# capacitance_touch_project.net
KiCad netlist of a schematic drawn in EAGLE
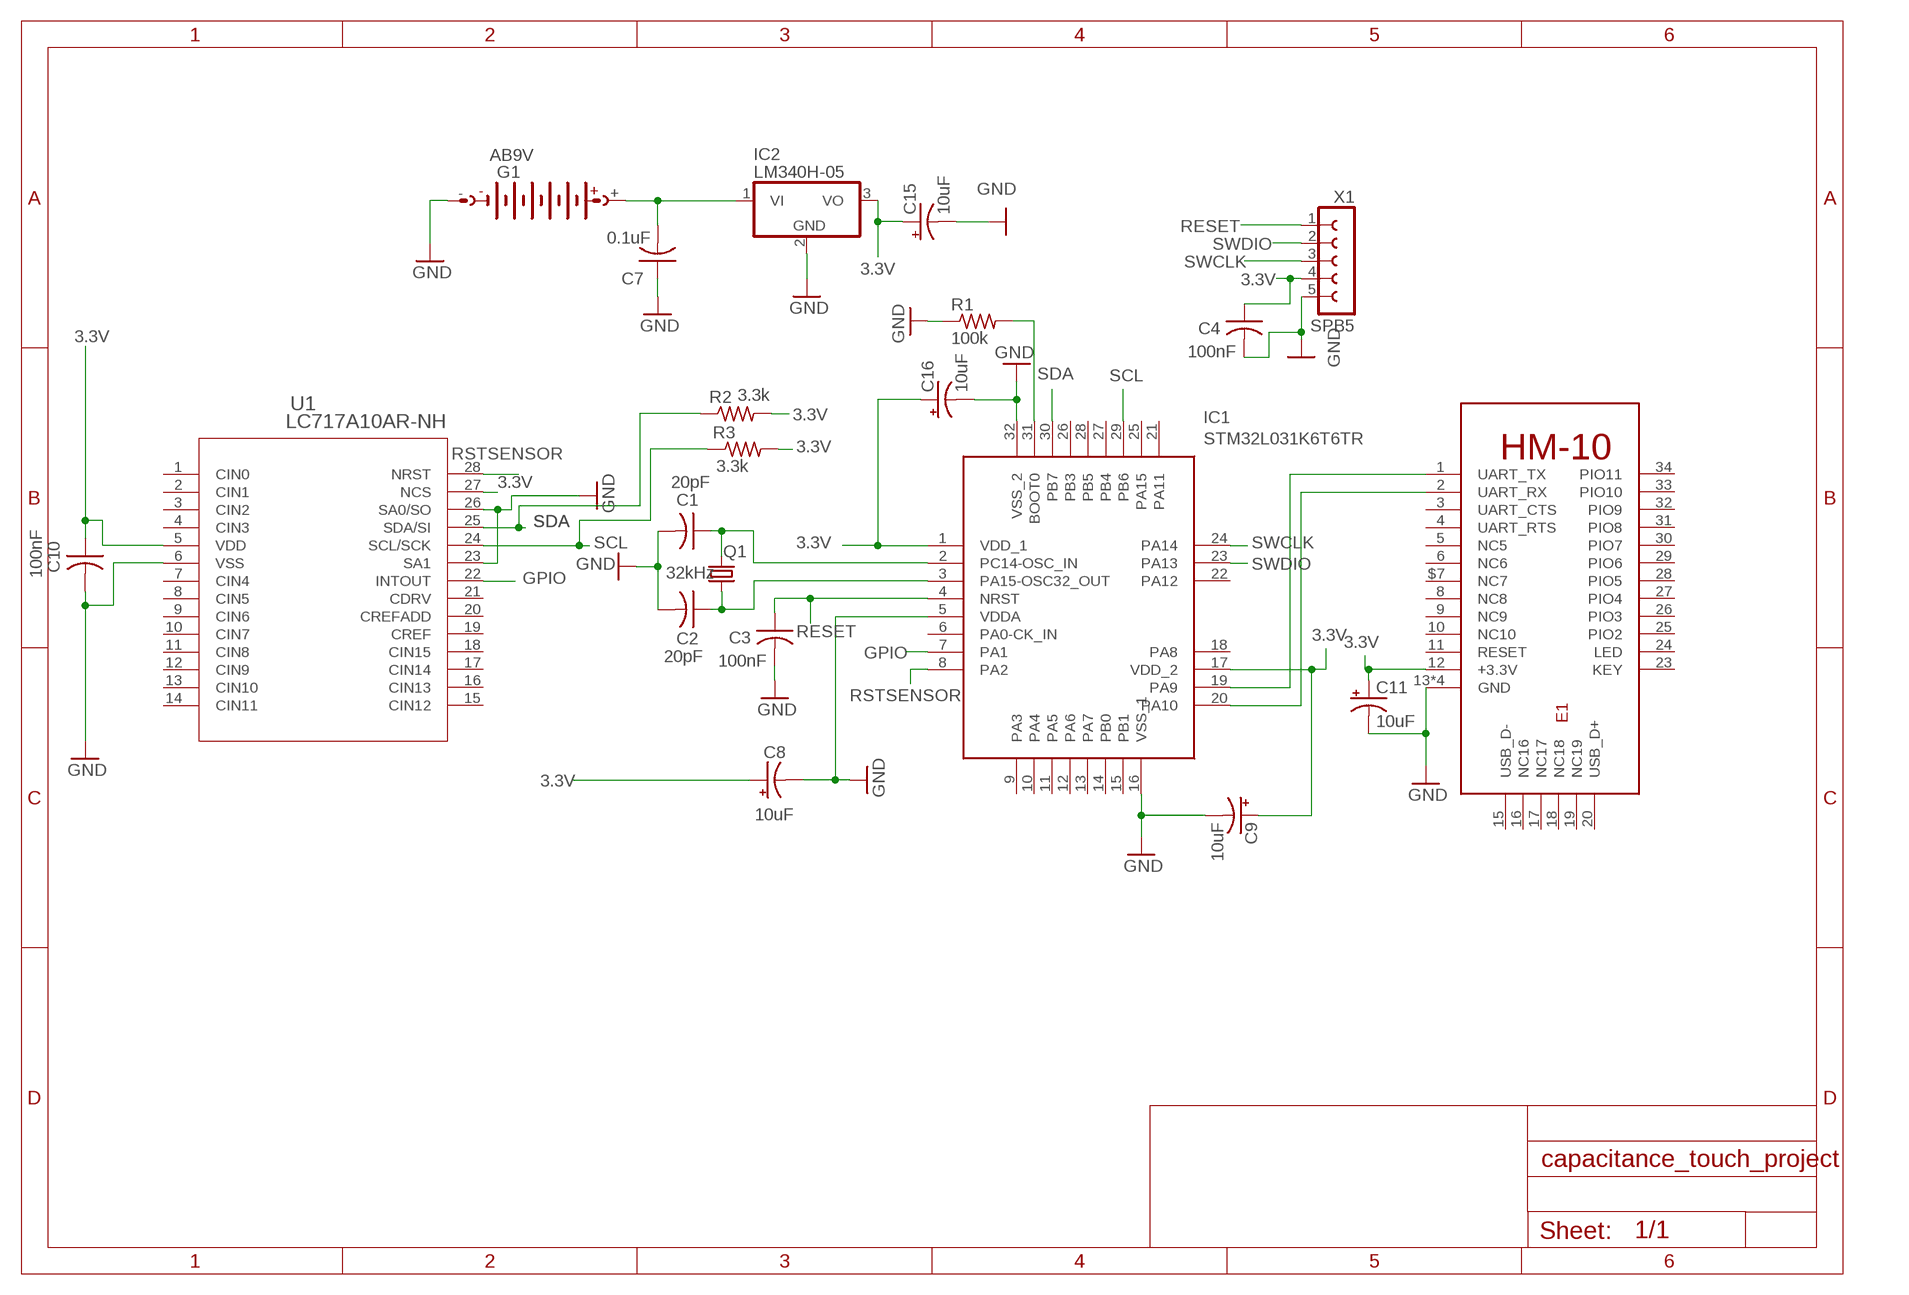
[diagram p0: schematic, sheet 1]

(export (version "E")
  (design (tool "Eeschema 10.0.6"))
  (components
    (comp (ref "C1")
      (value "20pF")
      (footprint "eagle-import:C0805")
      (libsource (lib "eagle-import") (part "C-USC0805"))
    )
    (comp (ref "C2")
      (value "20pF")
      (footprint "eagle-import:C0805")
      (libsource (lib "eagle-import") (part "C-USC0805"))
    )
    (comp (ref "C3")
      (value "100nF")
      (footprint "eagle-import:C0805")
      (libsource (lib "eagle-import") (part "C-USC0805"))
    )
    (comp (ref "C4")
      (value "100nF")
      (footprint "eagle-import:C0805")
      (libsource (lib "eagle-import") (part "C-USC0805"))
    )
    (comp (ref "C7")
      (value "0.1uF")
      (footprint "eagle-import:C0805")
      (libsource (lib "eagle-import") (part "C-USC0805"))
    )
    (comp (ref "C8")
      (value "10uF")
      (footprint "eagle-import:E2-5")
      (libsource (lib "eagle-import") (part "CPOL-USE2-5"))
    )
    (comp (ref "C9")
      (value "10uF")
      (footprint "eagle-import:E2-5")
      (libsource (lib "eagle-import") (part "CPOL-USE2-5"))
    )
    (comp (ref "C10")
      (value "100nF")
      (footprint "eagle-import:C0805")
      (libsource (lib "eagle-import") (part "C-USC0805"))
    )
    (comp (ref "C11")
      (value "10uF")
      (footprint "eagle-import:E2-5")
      (libsource (lib "eagle-import") (part "CPOL-USE2-5"))
    )
    (comp (ref "C15")
      (value "10uF")
      (footprint "eagle-import:E2-5")
      (libsource (lib "eagle-import") (part "CPOL-USE2-5"))
    )
    (comp (ref "C16")
      (value "10uF")
      (footprint "eagle-import:E2-5")
      (libsource (lib "eagle-import") (part "CPOL-USE2-5"))
    )
    (comp (ref "E1")
      (value "HM-10-BOARD")
      (footprint "eagle-import:26.9X13X2.2_BOARD")
      (libsource (lib "eagle-import") (part "HM-10-BOARD"))
    )
    (comp (ref "G1")
      (value "AB9V")
      (footprint "eagle-import:AB9V")
      (libsource (lib "eagle-import") (part "AB9V"))
    )
    (comp (ref "IC1")
      (value "STM32L031K6T6TR")
      (footprint "eagle-import:QFP80P900X900X160-32N")
      (fields (field (name "MOUSER_PART_NUMBER") "511-STM32L031K6T6TR"))
      (libsource (lib "eagle-import") (part "STM32L031K6T6TR"))
    )
    (comp (ref "IC2")
      (value "LM340H-05")
      (footprint "eagle-import:TO220H")
      (libsource (lib "eagle-import") (part "LM340?-H05"))
    )
    (comp (ref "Q1")
      (value "32kHz")
      (footprint "eagle-import:HC49_S")
      (libsource (lib "eagle-import") (part "CRYSTALHC49S"))
    )
    (comp (ref "R1")
      (value "100k")
      (footprint "eagle-import:0204_7")
      (libsource (lib "eagle-import") (part "R-US_0204/7"))
    )
    (comp (ref "R2")
      (value "3.3k")
      (footprint "eagle-import:0204_7")
      (libsource (lib "eagle-import") (part "R-US_0204/7"))
    )
    (comp (ref "R3")
      (value "3.3k")
      (footprint "eagle-import:0204_7")
      (libsource (lib "eagle-import") (part "R-US_0204/7"))
    )
    (comp (ref "U1")
      (value "LC717A10AR-NH")
      (footprint "eagle-import:VCT28_3P5X3P5_ONS")
      (fields (field (name "COPYRIGHT") "Copyright (C) 2018 Accelerated Designs. All rights reserved"))
      (libsource (lib "eagle-import") (part "LC717A10AR-NH"))
    )
    (comp (ref "X1")
      (value "SPB5")
      (footprint "eagle-import:SPB5")
      (libsource (lib "eagle-import") (part "SPB5"))
    )
  )
  (nets
    (net (code "1") (name "/3.3V") (class "Default")
      (node (ref "C10") (pin "1") (pinfunction "1_1") (pintype "passive"))
      (node (ref "C11") (pin "+") (pinfunction "+_+") (pintype "passive"))
      (node (ref "C15") (pin "+") (pinfunction "+_+") (pintype "passive"))
      (node (ref "C16") (pin "+") (pinfunction "+_+") (pintype "passive"))
      (node (ref "C4") (pin "1") (pinfunction "1_1") (pintype "passive"))
      (node (ref "C8") (pin "+") (pinfunction "+_+") (pintype "passive"))
      (node (ref "C9") (pin "+") (pinfunction "+_+") (pintype "passive"))
      (node (ref "E1") (pin "12") (pinfunction "+3.3V_12") (pintype "bidirectional"))
      (node (ref "IC1") (pin "1") (pinfunction "VDD_1_1") (pintype "bidirectional"))
      (node (ref "IC1") (pin "17") (pinfunction "VDD_2_17") (pintype "bidirectional"))
      (node (ref "IC2") (pin "3") (pinfunction "VO_3") (pintype "passive"))
      (node (ref "R2") (pin "2") (pinfunction "2_2") (pintype "passive"))
      (node (ref "R3") (pin "2") (pinfunction "2_2") (pintype "passive"))
      (node (ref "U1") (pin "27") (pinfunction "NCS_27") (pintype "input"))
      (node (ref "U1") (pin "5") (pinfunction "VDD_5") (pintype "power_in"))
      (node (ref "X1") (pin "4") (pinfunction "4_4") (pintype "passive"))
    )
    (net (code "2") (name "/GPIO") (class "Default")
      (node (ref "IC1") (pin "7") (pinfunction "PA1_7") (pintype "bidirectional"))
      (node (ref "U1") (pin "22") (pinfunction "INTOUT_22") (pintype "output"))
    )
    (net (code "3") (name "/RESET") (class "Default")
      (node (ref "C3") (pin "1") (pinfunction "1_1") (pintype "passive"))
      (node (ref "IC1") (pin "4") (pinfunction "NRST_4") (pintype "bidirectional"))
      (node (ref "X1") (pin "1") (pinfunction "1_1") (pintype "passive"))
    )
    (net (code "4") (name "/RSTSENSOR") (class "Default")
      (node (ref "IC1") (pin "8") (pinfunction "PA2_8") (pintype "bidirectional"))
      (node (ref "U1") (pin "28") (pinfunction "NRST_28") (pintype "input"))
    )
    (net (code "5") (name "/SCL") (class "Default")
      (node (ref "IC1") (pin "29") (pinfunction "PB6_29") (pintype "bidirectional"))
      (node (ref "R3") (pin "1") (pinfunction "1_1") (pintype "passive"))
      (node (ref "U1") (pin "24") (pinfunction "SCL/SCK_24") (pintype "input"))
    )
    (net (code "6") (name "/SDA") (class "Default")
      (node (ref "IC1") (pin "30") (pinfunction "PB7_30") (pintype "bidirectional"))
      (node (ref "R2") (pin "1") (pinfunction "1_1") (pintype "passive"))
      (node (ref "U1") (pin "25") (pinfunction "SDA/SI_25") (pintype "bidirectional"))
    )
    (net (code "7") (name "/SWCLK") (class "Default")
      (node (ref "IC1") (pin "24") (pinfunction "PA14_24") (pintype "bidirectional"))
      (node (ref "X1") (pin "3") (pinfunction "3_3") (pintype "passive"))
    )
    (net (code "8") (name "/SWDIO") (class "Default")
      (node (ref "IC1") (pin "23") (pinfunction "PA13_23") (pintype "bidirectional"))
      (node (ref "X1") (pin "2") (pinfunction "2_2") (pintype "passive"))
    )
    (net (code "9") (name "GND") (class "Default")
      (node (ref "C1") (pin "2") (pinfunction "2_2") (pintype "passive"))
      (node (ref "C10") (pin "2") (pinfunction "2_2") (pintype "passive"))
      (node (ref "C11") (pin "-") (pinfunction "-_-") (pintype "passive"))
      (node (ref "C15") (pin "-") (pinfunction "-_-") (pintype "passive"))
      (node (ref "C16") (pin "-") (pinfunction "-_-") (pintype "passive"))
      (node (ref "C2") (pin "2") (pinfunction "2_2") (pintype "passive"))
      (node (ref "C3") (pin "2") (pinfunction "2_2") (pintype "passive"))
      (node (ref "C4") (pin "2") (pinfunction "2_2") (pintype "passive"))
      (node (ref "C7") (pin "1") (pinfunction "1_1") (pintype "passive"))
      (node (ref "C8") (pin "-") (pinfunction "-_-") (pintype "passive"))
      (node (ref "C9") (pin "-") (pinfunction "-_-") (pintype "passive"))
      (node (ref "E1") (pin "13") (pinfunction "GND_13") (pintype "bidirectional"))
      (node (ref "E1") (pin "14") (pinfunction "GND_14") (pintype "bidirectional"))
      (node (ref "E1") (pin "21") (pinfunction "GND_21") (pintype "bidirectional"))
      (node (ref "E1") (pin "22") (pinfunction "GND_22") (pintype "bidirectional"))
      (node (ref "G1") (pin "-") (pinfunction "-_-") (pintype "passive"))
      (node (ref "IC1") (pin "16") (pinfunction "VSS_1_16") (pintype "bidirectional"))
      (node (ref "IC1") (pin "32") (pinfunction "VSS_2_32") (pintype "bidirectional"))
      (node (ref "IC1") (pin "5") (pinfunction "VDDA_5") (pintype "bidirectional"))
      (node (ref "IC2") (pin "2") (pinfunction "GND_2") (pintype "passive"))
      (node (ref "R1") (pin "1") (pinfunction "1_1") (pintype "passive"))
      (node (ref "U1") (pin "23") (pinfunction "SA1_23") (pintype "input"))
      (node (ref "U1") (pin "26") (pinfunction "SA0/SO_26") (pintype "bidirectional"))
      (node (ref "U1") (pin "6") (pinfunction "VSS_6") (pintype "passive"))
      (node (ref "X1") (pin "5") (pinfunction "5_5") (pintype "passive"))
    )
    (net (code "10") (name "Net-(E1-UART_RX)") (class "Default")
      (node (ref "E1") (pin "2") (pinfunction "UART_RX_2") (pintype "bidirectional"))
      (node (ref "IC1") (pin "20") (pinfunction "PA10_20") (pintype "bidirectional"))
    )
    (net (code "11") (name "Net-(E1-UART_TX)") (class "Default")
      (node (ref "E1") (pin "1") (pinfunction "UART_TX_1") (pintype "bidirectional"))
      (node (ref "IC1") (pin "19") (pinfunction "PA9_19") (pintype "bidirectional"))
    )
    (net (code "12") (name "Net-(IC1-BOOT0)") (class "Default")
      (node (ref "IC1") (pin "31") (pinfunction "BOOT0_31") (pintype "bidirectional"))
      (node (ref "R1") (pin "2") (pinfunction "2_2") (pintype "passive"))
    )
    (net (code "13") (name "Net-(IC1-PA15-OSC32_OUT)") (class "Default")
      (node (ref "C2") (pin "1") (pinfunction "1_1") (pintype "passive"))
      (node (ref "IC1") (pin "3") (pinfunction "PA15-OSC32_OUT_3") (pintype "bidirectional"))
      (node (ref "Q1") (pin "1") (pinfunction "1_1") (pintype "passive"))
    )
    (net (code "14") (name "Net-(IC1-PC14-OSC_IN)") (class "Default")
      (node (ref "C1") (pin "1") (pinfunction "1_1") (pintype "passive"))
      (node (ref "IC1") (pin "2") (pinfunction "PC14-OSC_IN_2") (pintype "bidirectional"))
      (node (ref "Q1") (pin "2") (pinfunction "2_2") (pintype "passive"))
    )
    (net (code "15") (name "Net-(IC2-VI)") (class "Default")
      (node (ref "C7") (pin "2") (pinfunction "2_2") (pintype "passive"))
      (node (ref "G1") (pin "+") (pinfunction "+_+") (pintype "passive"))
      (node (ref "IC2") (pin "1") (pinfunction "VI_1") (pintype "input"))
    )
    (net (code "16") (name "unconnected-(E1-KEY-Pad23)") (class "Default")
      (node (ref "E1") (pin "23") (pinfunction "KEY_23") (pintype "bidirectional"))
    )
    (net (code "17") (name "unconnected-(E1-LED-Pad24)") (class "Default")
      (node (ref "E1") (pin "24") (pinfunction "LED_24") (pintype "bidirectional"))
    )
    (net (code "18") (name "unconnected-(E1-NC5-Pad5)") (class "Default")
      (node (ref "E1") (pin "5") (pinfunction "NC5_5") (pintype "bidirectional"))
    )
    (net (code "19") (name "unconnected-(E1-NC6-Pad6)") (class "Default")
      (node (ref "E1") (pin "6") (pinfunction "NC6_6") (pintype "bidirectional"))
    )
    (net (code "20") (name "unconnected-(E1-NC7-Pad$7)") (class "Default")
      (node (ref "E1") (pin "$7") (pinfunction "NC7_$7") (pintype "bidirectional"))
    )
    (net (code "21") (name "unconnected-(E1-NC8-Pad8)") (class "Default")
      (node (ref "E1") (pin "8") (pinfunction "NC8_8") (pintype "bidirectional"))
    )
    (net (code "22") (name "unconnected-(E1-NC9-Pad9)") (class "Default")
      (node (ref "E1") (pin "9") (pinfunction "NC9_9") (pintype "bidirectional"))
    )
    (net (code "23") (name "unconnected-(E1-NC10-Pad10)") (class "Default")
      (node (ref "E1") (pin "10") (pinfunction "NC10_10") (pintype "bidirectional"))
    )
    (net (code "24") (name "unconnected-(E1-NC16-Pad16)") (class "Default")
      (node (ref "E1") (pin "16") (pinfunction "NC16_16") (pintype "bidirectional"))
    )
    (net (code "25") (name "unconnected-(E1-NC17-Pad17)") (class "Default")
      (node (ref "E1") (pin "17") (pinfunction "NC17_17") (pintype "bidirectional"))
    )
    (net (code "26") (name "unconnected-(E1-NC18-Pad18)") (class "Default")
      (node (ref "E1") (pin "18") (pinfunction "NC18_18") (pintype "bidirectional"))
    )
    (net (code "27") (name "unconnected-(E1-NC19-Pad19)") (class "Default")
      (node (ref "E1") (pin "19") (pinfunction "NC19_19") (pintype "bidirectional"))
    )
    (net (code "28") (name "unconnected-(E1-PIO2-Pad25)") (class "Default")
      (node (ref "E1") (pin "25") (pinfunction "PIO2_25") (pintype "bidirectional"))
    )
    (net (code "29") (name "unconnected-(E1-PIO3-Pad26)") (class "Default")
      (node (ref "E1") (pin "26") (pinfunction "PIO3_26") (pintype "bidirectional"))
    )
    (net (code "30") (name "unconnected-(E1-PIO4-Pad27)") (class "Default")
      (node (ref "E1") (pin "27") (pinfunction "PIO4_27") (pintype "bidirectional"))
    )
    (net (code "31") (name "unconnected-(E1-PIO5-Pad28)") (class "Default")
      (node (ref "E1") (pin "28") (pinfunction "PIO5_28") (pintype "bidirectional"))
    )
    (net (code "32") (name "unconnected-(E1-PIO6-Pad29)") (class "Default")
      (node (ref "E1") (pin "29") (pinfunction "PIO6_29") (pintype "bidirectional"))
    )
    (net (code "33") (name "unconnected-(E1-PIO7-Pad30)") (class "Default")
      (node (ref "E1") (pin "30") (pinfunction "PIO7_30") (pintype "bidirectional"))
    )
    (net (code "34") (name "unconnected-(E1-PIO8-Pad31)") (class "Default")
      (node (ref "E1") (pin "31") (pinfunction "PIO8_31") (pintype "bidirectional"))
    )
    (net (code "35") (name "unconnected-(E1-PIO9-Pad32)") (class "Default")
      (node (ref "E1") (pin "32") (pinfunction "PIO9_32") (pintype "bidirectional"))
    )
    (net (code "36") (name "unconnected-(E1-PIO10-Pad33)") (class "Default")
      (node (ref "E1") (pin "33") (pinfunction "PIO10_33") (pintype "bidirectional"))
    )
    (net (code "37") (name "unconnected-(E1-PIO11-Pad34)") (class "Default")
      (node (ref "E1") (pin "34") (pinfunction "PIO11_34") (pintype "bidirectional"))
    )
    (net (code "38") (name "unconnected-(E1-RESET-Pad11)") (class "Default")
      (node (ref "E1") (pin "11") (pinfunction "RESET_11") (pintype "bidirectional"))
    )
    (net (code "39") (name "unconnected-(E1-UART_CTS-Pad3)") (class "Default")
      (node (ref "E1") (pin "3") (pinfunction "UART_CTS_3") (pintype "bidirectional"))
    )
    (net (code "40") (name "unconnected-(E1-UART_RTS-Pad4)") (class "Default")
      (node (ref "E1") (pin "4") (pinfunction "UART_RTS_4") (pintype "bidirectional"))
    )
    (net (code "41") (name "unconnected-(E1-USB_D+-Pad20)") (class "Default")
      (node (ref "E1") (pin "20") (pinfunction "USB_D+_20") (pintype "bidirectional"))
    )
    (net (code "42") (name "unconnected-(E1-USB_D--Pad15)") (class "Default")
      (node (ref "E1") (pin "15") (pinfunction "USB_D-_15") (pintype "bidirectional"))
    )
    (net (code "43") (name "unconnected-(IC1-PA0-CK_IN-Pad6)") (class "Default")
      (node (ref "IC1") (pin "6") (pinfunction "PA0-CK_IN_6") (pintype "bidirectional"))
    )
    (net (code "44") (name "unconnected-(IC1-PA3-Pad9)") (class "Default")
      (node (ref "IC1") (pin "9") (pinfunction "PA3_9") (pintype "bidirectional"))
    )
    (net (code "45") (name "unconnected-(IC1-PA4-Pad10)") (class "Default")
      (node (ref "IC1") (pin "10") (pinfunction "PA4_10") (pintype "bidirectional"))
    )
    (net (code "46") (name "unconnected-(IC1-PA5-Pad11)") (class "Default")
      (node (ref "IC1") (pin "11") (pinfunction "PA5_11") (pintype "bidirectional"))
    )
    (net (code "47") (name "unconnected-(IC1-PA6-Pad12)") (class "Default")
      (node (ref "IC1") (pin "12") (pinfunction "PA6_12") (pintype "bidirectional"))
    )
    (net (code "48") (name "unconnected-(IC1-PA7-Pad13)") (class "Default")
      (node (ref "IC1") (pin "13") (pinfunction "PA7_13") (pintype "bidirectional"))
    )
    (net (code "49") (name "unconnected-(IC1-PA8-Pad18)") (class "Default")
      (node (ref "IC1") (pin "18") (pinfunction "PA8_18") (pintype "bidirectional"))
    )
    (net (code "50") (name "unconnected-(IC1-PA11-Pad21)") (class "Default")
      (node (ref "IC1") (pin "21") (pinfunction "PA11_21") (pintype "bidirectional"))
    )
    (net (code "51") (name "unconnected-(IC1-PA12-Pad22)") (class "Default")
      (node (ref "IC1") (pin "22") (pinfunction "PA12_22") (pintype "bidirectional"))
    )
    (net (code "52") (name "unconnected-(IC1-PA15-Pad25)") (class "Default")
      (node (ref "IC1") (pin "25") (pinfunction "PA15_25") (pintype "bidirectional"))
    )
    (net (code "53") (name "unconnected-(IC1-PB0-Pad14)") (class "Default")
      (node (ref "IC1") (pin "14") (pinfunction "PB0_14") (pintype "bidirectional"))
    )
    (net (code "54") (name "unconnected-(IC1-PB1-Pad15)") (class "Default")
      (node (ref "IC1") (pin "15") (pinfunction "PB1_15") (pintype "bidirectional"))
    )
    (net (code "55") (name "unconnected-(IC1-PB3-Pad26)") (class "Default")
      (node (ref "IC1") (pin "26") (pinfunction "PB3_26") (pintype "bidirectional"))
    )
    (net (code "56") (name "unconnected-(IC1-PB4-Pad27)") (class "Default")
      (node (ref "IC1") (pin "27") (pinfunction "PB4_27") (pintype "bidirectional"))
    )
    (net (code "57") (name "unconnected-(IC1-PB5-Pad28)") (class "Default")
      (node (ref "IC1") (pin "28") (pinfunction "PB5_28") (pintype "bidirectional"))
    )
    (net (code "58") (name "unconnected-(U1-CDRV-Pad21)") (class "Default")
      (node (ref "U1") (pin "21") (pinfunction "CDRV_21") (pintype "output"))
    )
    (net (code "59") (name "unconnected-(U1-CIN0-Pad1)") (class "Default")
      (node (ref "U1") (pin "1") (pinfunction "CIN0_1") (pintype "bidirectional"))
    )
    (net (code "60") (name "unconnected-(U1-CIN1-Pad2)") (class "Default")
      (node (ref "U1") (pin "2") (pinfunction "CIN1_2") (pintype "bidirectional"))
    )
    (net (code "61") (name "unconnected-(U1-CIN2-Pad3)") (class "Default")
      (node (ref "U1") (pin "3") (pinfunction "CIN2_3") (pintype "bidirectional"))
    )
    (net (code "62") (name "unconnected-(U1-CIN3-Pad4)") (class "Default")
      (node (ref "U1") (pin "4") (pinfunction "CIN3_4") (pintype "bidirectional"))
    )
    (net (code "63") (name "unconnected-(U1-CIN4-Pad7)") (class "Default")
      (node (ref "U1") (pin "7") (pinfunction "CIN4_7") (pintype "bidirectional"))
    )
    (net (code "64") (name "unconnected-(U1-CIN5-Pad8)") (class "Default")
      (node (ref "U1") (pin "8") (pinfunction "CIN5_8") (pintype "bidirectional"))
    )
    (net (code "65") (name "unconnected-(U1-CIN6-Pad9)") (class "Default")
      (node (ref "U1") (pin "9") (pinfunction "CIN6_9") (pintype "bidirectional"))
    )
    (net (code "66") (name "unconnected-(U1-CIN7-Pad10)") (class "Default")
      (node (ref "U1") (pin "10") (pinfunction "CIN7_10") (pintype "bidirectional"))
    )
    (net (code "67") (name "unconnected-(U1-CIN8-Pad11)") (class "Default")
      (node (ref "U1") (pin "11") (pinfunction "CIN8_11") (pintype "bidirectional"))
    )
    (net (code "68") (name "unconnected-(U1-CIN9-Pad12)") (class "Default")
      (node (ref "U1") (pin "12") (pinfunction "CIN9_12") (pintype "bidirectional"))
    )
    (net (code "69") (name "unconnected-(U1-CIN10-Pad13)") (class "Default")
      (node (ref "U1") (pin "13") (pinfunction "CIN10_13") (pintype "bidirectional"))
    )
    (net (code "70") (name "unconnected-(U1-CIN11-Pad14)") (class "Default")
      (node (ref "U1") (pin "14") (pinfunction "CIN11_14") (pintype "bidirectional"))
    )
    (net (code "71") (name "unconnected-(U1-CIN12-Pad15)") (class "Default")
      (node (ref "U1") (pin "15") (pinfunction "CIN12_15") (pintype "bidirectional"))
    )
    (net (code "72") (name "unconnected-(U1-CIN13-Pad16)") (class "Default")
      (node (ref "U1") (pin "16") (pinfunction "CIN13_16") (pintype "bidirectional"))
    )
    (net (code "73") (name "unconnected-(U1-CIN14-Pad17)") (class "Default")
      (node (ref "U1") (pin "17") (pinfunction "CIN14_17") (pintype "bidirectional"))
    )
    (net (code "74") (name "unconnected-(U1-CIN15-Pad18)") (class "Default")
      (node (ref "U1") (pin "18") (pinfunction "CIN15_18") (pintype "bidirectional"))
    )
    (net (code "75") (name "unconnected-(U1-CREF-Pad19)") (class "Default")
      (node (ref "U1") (pin "19") (pinfunction "CREF_19") (pintype "bidirectional"))
    )
    (net (code "76") (name "unconnected-(U1-CREFADD-Pad20)") (class "Default")
      (node (ref "U1") (pin "20") (pinfunction "CREFADD_20") (pintype "bidirectional"))
    )
  )
)
